# Sintetizador2.net
KiCad netlist of a schematic drawn in Altium Designer
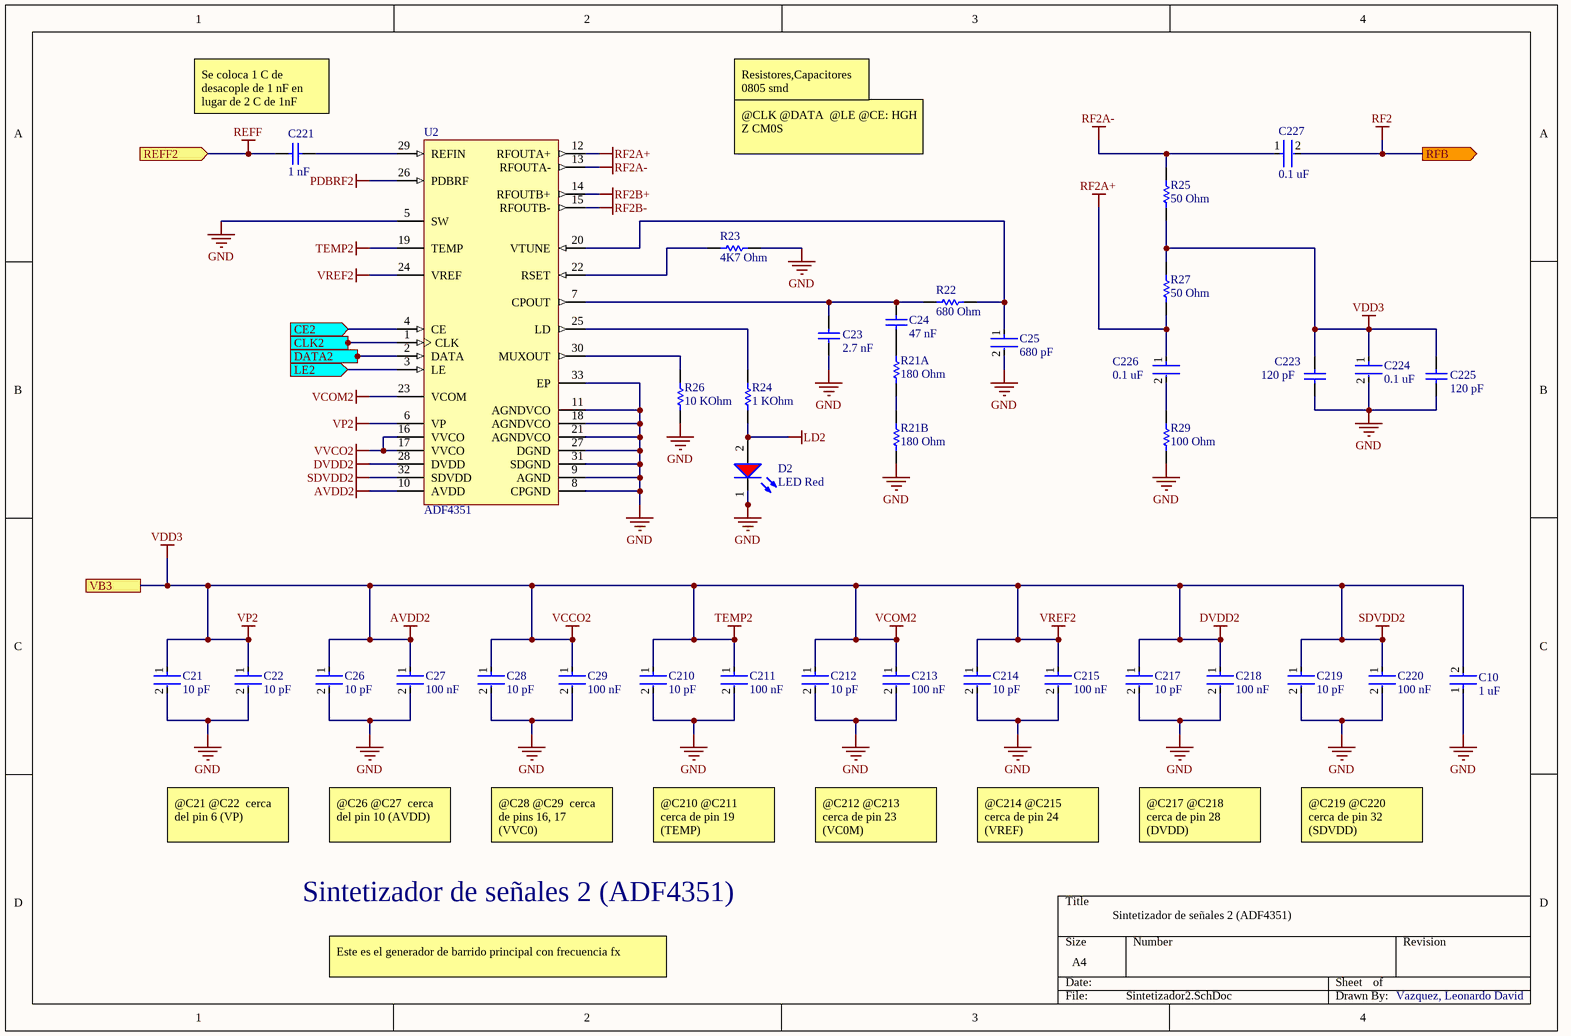
[diagram p0: Sintetizador2.SchDoc]

(export (version "E")
  (design (tool "Eeschema 10.0.6"))
  (components
    (comp (ref "C10")
      (value "1 uF")
      (footprint "FP-CC0805-0_85-MFG")
      (description "CAP CER 0.1UF 50V X7R 0805")
      (fields (field (name "TOLERANCE") "0.1") (field (name "MANUFACTURER PART NUMBER") "CC0805KRX7R9BB104"))
      (libsource (lib "Altium Content Vault") (part "11868f565c42a9108669ba33697ecf6"))
    )
    (comp (ref "C21")
      (value "10 pF")
      (footprint "FP-CL21-IPC_C")
      (description "CL21 Series 0805 10pF 100V ±0.25pF Tolerance C0G Multilayer Ceramic Chip Capacitor")
      (fields (field (name "VOLTAGE") "100V"))
      (libsource (lib "Altium Content Vault") (part "b4654b650e69147ec39a6b967a45e02"))
    )
    (comp (ref "C22")
      (value "10 pF")
      (footprint "FP-CL21-IPC_C")
      (description "CAP CER 0.1UF 50V X7R 0805")
      (fields (field (name "TOLERANCE") "0.1") (field (name "MANUFACTURER PART NUMBER") "CC0805KRX7R9BB104"))
      (libsource (lib "Altium Content Vault") (part "11868f565c42a9108669ba33697ecf6"))
    )
    (comp (ref "C23")
      (value "2.7 nF")
      (footprint "CAPC2013X130X50NL20T20")
      (fields (field (name "PART NUMBER") "CDR31BX272BKMSAJ") (field (name "MANUFACTURER") "Vitramon"))
      (libsource (lib "Altium Content Vault") (part "CAP"))
    )
    (comp (ref "C24")
      (value "47 nF")
      (footprint "CAPC2013X100X50ML20T25")
      (fields (field (name "MANUFACTURER") "Kemet") (field (name "PART NUMBER") "C0805F473K5RACTU"))
      (libsource (lib "Altium Content Vault") (part "CAP"))
    )
    (comp (ref "C25")
      (value "680 pF")
      (footprint "FP-C0805C-DN-MFG")
      (description "CAP CER 680PF 100V 5% NP0 0805")
      (fields
        (field (name "OCTOPART") "https://octopart.com/c0805c681j1gactu-kemet-8375796")
        (field (name "MANUFACTURER") "KEMET")
      )
      (libsource (lib "Altium Content Vault") (part "b4654b650e69147ec39a6b967a45e02"))
    )
    (comp (ref "C26")
      (value "10 pF")
      (footprint "FP-CL21-IPC_C")
      (description "CL21 Series 0805 10pF 100V ±0.25pF Tolerance C0G Multilayer Ceramic Chip Capacitor")
      (fields (field (name "VOLTAGE") "100V"))
      (libsource (lib "Altium Content Vault") (part "b4654b650e69147ec39a6b967a45e02"))
    )
    (comp (ref "C27")
      (value "100 nF")
      (footprint "FP-CL21-IPC_C")
      (description "CAP CER 0.1UF 50V X7R 0805")
      (fields (field (name "TOLERANCE") "0.1") (field (name "MANUFACTURER PART NUMBER") "CC0805KRX7R9BB104"))
      (libsource (lib "Altium Content Vault") (part "11868f565c42a9108669ba33697ecf6"))
    )
    (comp (ref "C28")
      (value "10 pF")
      (footprint "FP-CL21-IPC_C")
      (description "CL21 Series 0805 10pF 100V ±0.25pF Tolerance C0G Multilayer Ceramic Chip Capacitor")
      (fields (field (name "VOLTAGE") "100V"))
      (libsource (lib "Altium Content Vault") (part "b4654b650e69147ec39a6b967a45e02"))
    )
    (comp (ref "C29")
      (value "100 nF")
      (footprint "FP-CL21-IPC_C")
      (description "CAP CER 0.1UF 50V X7R 0805")
      (fields (field (name "TOLERANCE") "0.1") (field (name "MANUFACTURER PART NUMBER") "CC0805KRX7R9BB104"))
      (libsource (lib "Altium Content Vault") (part "11868f565c42a9108669ba33697ecf6"))
    )
    (comp (ref "C210")
      (value "10 pF")
      (footprint "FP-CL21-IPC_C")
      (description "CL21 Series 0805 10pF 100V ±0.25pF Tolerance C0G Multilayer Ceramic Chip Capacitor")
      (fields (field (name "VOLTAGE") "100V"))
      (libsource (lib "Altium Content Vault") (part "b4654b650e69147ec39a6b967a45e02"))
    )
    (comp (ref "C211")
      (value "100 nF")
      (footprint "FP-CL21-IPC_C")
      (description "CAP CER 0.1UF 50V X7R 0805")
      (fields (field (name "TOLERANCE") "0.1") (field (name "MANUFACTURER PART NUMBER") "CC0805KRX7R9BB104"))
      (libsource (lib "Altium Content Vault") (part "11868f565c42a9108669ba33697ecf6"))
    )
    (comp (ref "C212")
      (value "10 pF")
      (footprint "FP-CL21-IPC_C")
      (description "CL21 Series 0805 10pF 100V ±0.25pF Tolerance C0G Multilayer Ceramic Chip Capacitor")
      (fields (field (name "VOLTAGE") "100V"))
      (libsource (lib "Altium Content Vault") (part "b4654b650e69147ec39a6b967a45e02"))
    )
    (comp (ref "C213")
      (value "100 nF")
      (footprint "FP-CL21-IPC_C")
      (description "CAP CER 0.1UF 50V X7R 0805")
      (fields (field (name "TOLERANCE") "0.1") (field (name "MANUFACTURER PART NUMBER") "CC0805KRX7R9BB104"))
      (libsource (lib "Altium Content Vault") (part "11868f565c42a9108669ba33697ecf6"))
    )
    (comp (ref "C214")
      (value "10 pF")
      (footprint "FP-CL21-IPC_C")
      (description "CL21 Series 0805 10pF 100V ±0.25pF Tolerance C0G Multilayer Ceramic Chip Capacitor")
      (fields (field (name "VOLTAGE") "100V"))
      (libsource (lib "Altium Content Vault") (part "b4654b650e69147ec39a6b967a45e02"))
    )
    (comp (ref "C215")
      (value "100 nF")
      (footprint "FP-CL21-IPC_C")
      (description "CAP CER 0.1UF 50V X7R 0805")
      (fields (field (name "TOLERANCE") "0.1") (field (name "MANUFACTURER PART NUMBER") "CC0805KRX7R9BB104"))
      (libsource (lib "Altium Content Vault") (part "11868f565c42a9108669ba33697ecf6"))
    )
    (comp (ref "C217")
      (value "10 pF")
      (footprint "FP-CL21-IPC_C")
      (description "CL21 Series 0805 10pF 100V ±0.25pF Tolerance C0G Multilayer Ceramic Chip Capacitor")
      (fields (field (name "VOLTAGE") "100V"))
      (libsource (lib "Altium Content Vault") (part "b4654b650e69147ec39a6b967a45e02"))
    )
    (comp (ref "C218")
      (value "100 nF")
      (footprint "FP-CL21-IPC_C")
      (description "CAP CER 0.1UF 50V X7R 0805")
      (fields (field (name "TOLERANCE") "0.1") (field (name "MANUFACTURER PART NUMBER") "CC0805KRX7R9BB104"))
      (libsource (lib "Altium Content Vault") (part "11868f565c42a9108669ba33697ecf6"))
    )
    (comp (ref "C219")
      (value "10 pF")
      (footprint "FP-CL21-IPC_C")
      (description "CL21 Series 0805 10pF 100V ±0.25pF Tolerance C0G Multilayer Ceramic Chip Capacitor")
      (fields (field (name "VOLTAGE") "100V"))
      (libsource (lib "Altium Content Vault") (part "b4654b650e69147ec39a6b967a45e02"))
    )
    (comp (ref "C220")
      (value "100 nF")
      (footprint "FP-CL21-IPC_C")
      (description "CAP CER 0.1UF 50V X7R 0805")
      (fields (field (name "TOLERANCE") "0.1") (field (name "MANUFACTURER PART NUMBER") "CC0805KRX7R9BB104"))
      (libsource (lib "Altium Content Vault") (part "11868f565c42a9108669ba33697ecf6"))
    )
    (comp (ref "C221")
      (value "1 nF")
      (footprint "CAPC2013X94X50NL20T25")
      (fields
        (field (name "MANUFACTURER") "AVX Interconnect / Elco")
        (field (name "PART NUMBER") "08051A102J4T2A")
      )
      (libsource (lib "Altium Content Vault") (part "CAP"))
    )
    (comp (ref "C223")
      (value "120 pF")
      (footprint "FP-CC0805-0_85-MFG")
      (fields (field (name "MANUFACTURER") "Kemet") (field (name "PART NUMBER") "C0805C101JCGACTU"))
      (libsource (lib "") (part "CAP_1"))
    )
    (comp (ref "C224")
      (value "0.1 uF")
      (footprint "FP-CC0805-0_85-MFG")
      (description "CAP CER 0.1UF 50V X7R 0805")
      (fields (field (name "TOLERANCE") "0.1") (field (name "MANUFACTURER PART NUMBER") "CC0805KRX7R9BB104"))
      (libsource (lib "Altium Content Vault") (part "11868f565c42a9108669ba33697ecf6"))
    )
    (comp (ref "C225")
      (value "120 pF")
      (footprint "FP-CC0805-0_85-MFG")
      (fields (field (name "MANUFACTURER") "Kemet") (field (name "PART NUMBER") "C0805C101JCGACTU"))
      (libsource (lib "") (part "CAP_1"))
    )
    (comp (ref "C226")
      (value "0.1 uF")
      (footprint "FP-CC0805-0_85-MFG")
      (description "CAP CER 0.1UF 50V X7R 0805")
      (fields (field (name "TOLERANCE") "0.1") (field (name "MANUFACTURER PART NUMBER") "CC0805KRX7R9BB104"))
      (libsource (lib "Altium Content Vault") (part "11868f565c42a9108669ba33697ecf6"))
    )
    (comp (ref "C227")
      (value "0.1 uF")
      (footprint "FP-CC0805-0_85-MFG")
      (description "CAP CER 0.1UF 50V X7R 0805")
      (fields (field (name "TOLERANCE") "0.1") (field (name "MANUFACTURER PART NUMBER") "CC0805KRX7R9BB104"))
      (libsource (lib "Altium Content Vault") (part "11868f565c42a9108669ba33697ecf6"))
    )
    (comp (ref "D2")
      (value "LED Red")
      (footprint "WL-SMCW_0805_150080xx75000")
      (libsource (lib "Altium Content Vault") (part "LED_Red_2A-1K"))
    )
    (comp (ref "R21A")
      (value "180 Ohm")
      (footprint "RESC2013X70X40ML20T20")
      (fields (field (name "MANUFACTURER") "Panasonic") (field (name "PART NUMBER") "ERJ-6ENF3600V"))
      (libsource (lib "Altium Content Vault") (part "RES"))
    )
    (comp (ref "R21B")
      (value "180 Ohm")
      (footprint "RESC2013X70X40ML20T20")
      (fields (field (name "MANUFACTURER") "Panasonic") (field (name "PART NUMBER") "ERJ-6ENF3600V"))
      (libsource (lib "") (part "RES_2"))
    )
    (comp (ref "R22")
      (value "680 Ohm")
      (footprint "RESC2013X70X40ML20T20")
      (fields (field (name "PART NUMBER") "ERJ6ENF6803V") (field (name "MANUFACTURER") "Panasonic"))
      (libsource (lib "") (part "RES_1"))
    )
    (comp (ref "R23")
      (value "4K7 Ohm")
      (footprint "RESC2013X70X40ML20T20")
      (fields (field (name "PART NUMBER") "ERJ6ENF6803V") (field (name "MANUFACTURER") "Panasonic"))
      (libsource (lib "") (part "RES_1"))
    )
    (comp (ref "R24")
      (value "1 KOhm")
      (footprint "RESC2013X60X40ML20T25")
      (fields (field (name "MANUFACTURER") "Panasonic") (field (name "PART NUMBER") "ERA6AEB101V"))
      (libsource (lib "") (part "RES_1"))
    )
    (comp (ref "R25")
      (value "50 Ohm")
      (footprint "RESC2013X60X40ML20T25")
      (fields (field (name "MANUFACTURER") "Panasonic") (field (name "PART NUMBER") "ERA6AEB101V"))
      (libsource (lib "") (part "RES_1"))
    )
    (comp (ref "R26")
      (value "10 KOhm")
      (footprint "RESC2013X60X40ML20T25")
      (fields (field (name "MANUFACTURER") "Panasonic") (field (name "PART NUMBER") "ERA6AEB101V"))
      (libsource (lib "") (part "RES_3"))
    )
    (comp (ref "R27")
      (value "50 Ohm")
      (footprint "RESC2013X60X40ML20T25")
      (fields (field (name "MANUFACTURER") "Panasonic") (field (name "PART NUMBER") "ERA6AEB101V"))
      (libsource (lib "") (part "RES_1"))
    )
    (comp (ref "R29")
      (value "100 Ohm")
      (footprint "RESC2013X60X40ML20T25")
      (fields (field (name "MANUFACTURER") "Panasonic") (field (name "PART NUMBER") "ERA6AEB101V"))
      (libsource (lib "") (part "RES_1"))
    )
    (comp (ref "U2")
      (value "ADF4351")
      (footprint "ADI-CP-32-2_L")
      (description "Wideband Synthesizer with Integrated VCO, CP-32-2, Pb-Free, 1500 Reel")
      (libsource (lib "Altium Content Vault") (part "ADI-ADF4351-CP-32-2"))
    )
  )
  (nets
    (net (code "1") (name "/CE2") (class "Default")
      (node (ref "U2") (pin "4") (pinfunction "CE_4") (pintype "input"))
    )
    (net (code "2") (name "/CLK2") (class "Default")
      (node (ref "U2") (pin "1") (pinfunction "CLK_1") (pintype "input"))
    )
    (net (code "3") (name "/DATA2") (class "Default")
      (node (ref "U2") (pin "2") (pinfunction "DATA_2") (pintype "input"))
    )
    (net (code "4") (name "/LE2") (class "Default")
      (node (ref "U2") (pin "3") (pinfunction "LE_3") (pintype "input"))
    )
    (net (code "5") (name "AVDD2") (class "Default")
      (node (ref "C10") (pin "2") (pinfunction "2_2") (pintype "passive"))
      (node (ref "C21") (pin "1") (pinfunction "1_1") (pintype "passive"))
      (node (ref "C210") (pin "1") (pinfunction "1_1") (pintype "passive"))
      (node (ref "C211") (pin "1") (pinfunction "1_1") (pintype "passive"))
      (node (ref "C212") (pin "1") (pinfunction "1_1") (pintype "passive"))
      (node (ref "C213") (pin "1") (pinfunction "1_1") (pintype "passive"))
      (node (ref "C214") (pin "1") (pinfunction "1_1") (pintype "passive"))
      (node (ref "C215") (pin "1") (pinfunction "1_1") (pintype "passive"))
      (node (ref "C217") (pin "1") (pinfunction "1_1") (pintype "passive"))
      (node (ref "C218") (pin "1") (pinfunction "1_1") (pintype "passive"))
      (node (ref "C219") (pin "1") (pinfunction "1_1") (pintype "passive"))
      (node (ref "C22") (pin "1") (pinfunction "1_1") (pintype "passive"))
      (node (ref "C220") (pin "1") (pinfunction "1_1") (pintype "passive"))
      (node (ref "C223") (pin "1") (pinfunction "1_1") (pintype "passive"))
      (node (ref "C224") (pin "1") (pinfunction "1_1") (pintype "passive"))
      (node (ref "C225") (pin "1") (pinfunction "1_1") (pintype "passive"))
      (node (ref "C26") (pin "1") (pinfunction "1_1") (pintype "passive"))
      (node (ref "C27") (pin "1") (pinfunction "1_1") (pintype "passive"))
      (node (ref "C28") (pin "1") (pinfunction "1_1") (pintype "passive"))
      (node (ref "C29") (pin "1") (pinfunction "1_1") (pintype "passive"))
      (node (ref "R25") (pin "2") (pinfunction "2_2") (pintype "passive"))
      (node (ref "R27") (pin "1") (pinfunction "1_1") (pintype "passive"))
      (node (ref "U2") (pin "10") (pinfunction "AVDD_10") (pintype "power_in"))
      (node (ref "U2") (pin "19") (pinfunction "TEMP_19") (pintype "passive"))
      (node (ref "U2") (pin "23") (pinfunction "VCOM_23") (pintype "passive"))
      (node (ref "U2") (pin "24") (pinfunction "VREF_24") (pintype "passive"))
      (node (ref "U2") (pin "28") (pinfunction "DVDD_28") (pintype "power_in"))
      (node (ref "U2") (pin "32") (pinfunction "SDVDD_32") (pintype "power_in"))
      (node (ref "U2") (pin "6") (pinfunction "VP_6") (pintype "power_in"))
    )
    (net (code "6") (name "GND") (class "Default")
      (node (ref "C10") (pin "1") (pinfunction "1_1") (pintype "passive"))
      (node (ref "C21") (pin "2") (pinfunction "2_2") (pintype "passive"))
      (node (ref "C210") (pin "2") (pinfunction "2_2") (pintype "passive"))
      (node (ref "C211") (pin "2") (pinfunction "2_2") (pintype "passive"))
      (node (ref "C212") (pin "2") (pinfunction "2_2") (pintype "passive"))
      (node (ref "C213") (pin "2") (pinfunction "2_2") (pintype "passive"))
      (node (ref "C214") (pin "2") (pinfunction "2_2") (pintype "passive"))
      (node (ref "C215") (pin "2") (pinfunction "2_2") (pintype "passive"))
      (node (ref "C217") (pin "2") (pinfunction "2_2") (pintype "passive"))
      (node (ref "C218") (pin "2") (pinfunction "2_2") (pintype "passive"))
      (node (ref "C219") (pin "2") (pinfunction "2_2") (pintype "passive"))
      (node (ref "C22") (pin "2") (pinfunction "2_2") (pintype "passive"))
      (node (ref "C220") (pin "2") (pinfunction "2_2") (pintype "passive"))
      (node (ref "C223") (pin "2") (pinfunction "2_2") (pintype "passive"))
      (node (ref "C224") (pin "2") (pinfunction "2_2") (pintype "passive"))
      (node (ref "C225") (pin "2") (pinfunction "2_2") (pintype "passive"))
      (node (ref "C23") (pin "1") (pinfunction "1_1") (pintype "passive"))
      (node (ref "C25") (pin "2") (pinfunction "2_2") (pintype "passive"))
      (node (ref "C26") (pin "2") (pinfunction "2_2") (pintype "passive"))
      (node (ref "C27") (pin "2") (pinfunction "2_2") (pintype "passive"))
      (node (ref "C28") (pin "2") (pinfunction "2_2") (pintype "passive"))
      (node (ref "C29") (pin "2") (pinfunction "2_2") (pintype "passive"))
      (node (ref "D2") (pin "1") (pinfunction "K_1") (pintype "passive"))
      (node (ref "R21B") (pin "1") (pinfunction "1_1") (pintype "passive"))
      (node (ref "R23") (pin "2") (pinfunction "2_2") (pintype "passive"))
      (node (ref "R26") (pin "2") (pinfunction "2_2") (pintype "passive"))
      (node (ref "R29") (pin "2") (pinfunction "2_2") (pintype "passive"))
      (node (ref "U2") (pin "11") (pinfunction "AGNDVCO_11") (pintype "power_in"))
      (node (ref "U2") (pin "18") (pinfunction "AGNDVCO_18") (pintype "power_in"))
      (node (ref "U2") (pin "21") (pinfunction "AGNDVCO_21") (pintype "power_in"))
      (node (ref "U2") (pin "27") (pinfunction "DGND_27") (pintype "power_in"))
      (node (ref "U2") (pin "31") (pinfunction "SDGND_31") (pintype "power_in"))
      (node (ref "U2") (pin "33") (pinfunction "EP_33") (pintype "power_in"))
      (node (ref "U2") (pin "5") (pinfunction "SW_5") (pintype "passive"))
      (node (ref "U2") (pin "8") (pinfunction "CPGND_8") (pintype "power_in"))
      (node (ref "U2") (pin "9") (pinfunction "AGND_9") (pintype "power_in"))
    )
    (net (code "7") (name "LD2") (class "Default")
      (node (ref "D2") (pin "2") (pinfunction "A_2") (pintype "passive"))
      (node (ref "R24") (pin "1") (pinfunction "1_1") (pintype "passive"))
    )
    (net (code "8") (name "Net-(C24-Pad1)") (class "Default")
      (node (ref "C24") (pin "1") (pinfunction "1_1") (pintype "passive"))
      (node (ref "R21A") (pin "2") (pinfunction "2_2") (pintype "passive"))
    )
    (net (code "9") (name "Net-(C226-Pad2)") (class "Default")
      (node (ref "C226") (pin "2") (pinfunction "2_2") (pintype "passive"))
      (node (ref "R29") (pin "1") (pinfunction "1_1") (pintype "passive"))
    )
    (net (code "10") (name "Net-(R21A-Pad2)") (class "Default")
      (node (ref "R21A") (pin "2") (pinfunction "2_2") (pintype "passive"))
      (node (ref "R21B") (pin "1") (pinfunction "1_1") (pintype "passive"))
    )
    (net (code "11") (name "Net-(U2-CPOUT)") (class "Default")
      (node (ref "C23") (pin "2") (pinfunction "2_2") (pintype "passive"))
      (node (ref "C24") (pin "2") (pinfunction "2_2") (pintype "passive"))
      (node (ref "R22") (pin "1") (pinfunction "1_1") (pintype "passive"))
      (node (ref "U2") (pin "7") (pinfunction "CPOUT_7") (pintype "output"))
    )
    (net (code "12") (name "Net-(U2-LD)") (class "Default")
      (node (ref "R24") (pin "2") (pinfunction "2_2") (pintype "passive"))
      (node (ref "U2") (pin "25") (pinfunction "LD_25") (pintype "output"))
    )
    (net (code "13") (name "Net-(U2-MUXOUT)") (class "Default")
      (node (ref "R26") (pin "1") (pinfunction "1_1") (pintype "passive"))
      (node (ref "U2") (pin "30") (pinfunction "MUXOUT_30") (pintype "output"))
    )
    (net (code "14") (name "Net-(U2-REFIN)") (class "Default")
      (node (ref "C221") (pin "2") (pinfunction "2_2") (pintype "passive"))
      (node (ref "U2") (pin "29") (pinfunction "REFIN_29") (pintype "input"))
    )
    (net (code "15") (name "Net-(U2-RSET)") (class "Default")
      (node (ref "R23") (pin "1") (pinfunction "1_1") (pintype "passive"))
      (node (ref "U2") (pin "22") (pinfunction "RSET_22") (pintype "input"))
    )
    (net (code "16") (name "Net-(U2-VTUNE)") (class "Default")
      (node (ref "C25") (pin "1") (pinfunction "1_1") (pintype "passive"))
      (node (ref "R22") (pin "2") (pinfunction "2_2") (pintype "passive"))
      (node (ref "U2") (pin "20") (pinfunction "VTUNE_20") (pintype "input"))
    )
    (net (code "17") (name "PDBRF2") (class "Default")
      (node (ref "U2") (pin "26") (pinfunction "PDBRF_26") (pintype "input"))
    )
    (net (code "18") (name "REFF") (class "Default")
      (node (ref "C221") (pin "1") (pinfunction "1_1") (pintype "passive"))
    )
    (net (code "19") (name "RF2") (class "Default")
      (node (ref "C227") (pin "2") (pinfunction "2_2") (pintype "passive"))
    )
    (net (code "20") (name "RF2A+") (class "Default")
      (node (ref "C226") (pin "1") (pinfunction "1_1") (pintype "passive"))
      (node (ref "R27") (pin "2") (pinfunction "2_2") (pintype "passive"))
      (node (ref "U2") (pin "12") (pinfunction "RFOUTA+_12") (pintype "output"))
    )
    (net (code "21") (name "RF2A-") (class "Default")
      (node (ref "C227") (pin "1") (pinfunction "1_1") (pintype "passive"))
      (node (ref "R25") (pin "1") (pinfunction "1_1") (pintype "passive"))
      (node (ref "U2") (pin "13") (pinfunction "RFOUTA-_13") (pintype "output"))
    )
    (net (code "22") (name "RF2B+") (class "Default")
      (node (ref "U2") (pin "14") (pinfunction "RFOUTB+_14") (pintype "output"))
    )
    (net (code "23") (name "RF2B-") (class "Default")
      (node (ref "U2") (pin "15") (pinfunction "RFOUTB-_15") (pintype "output"))
    )
    (net (code "24") (name "VVCO2") (class "Default")
      (node (ref "U2") (pin "16") (pinfunction "VVCO_16") (pintype "power_in"))
      (node (ref "U2") (pin "17") (pinfunction "VVCO_17") (pintype "power_in"))
    )
  )
)
